# POWER_SUPPLY_20-100V_Relay.net
KiCad netlist of a schematic drawn in Altium Designer
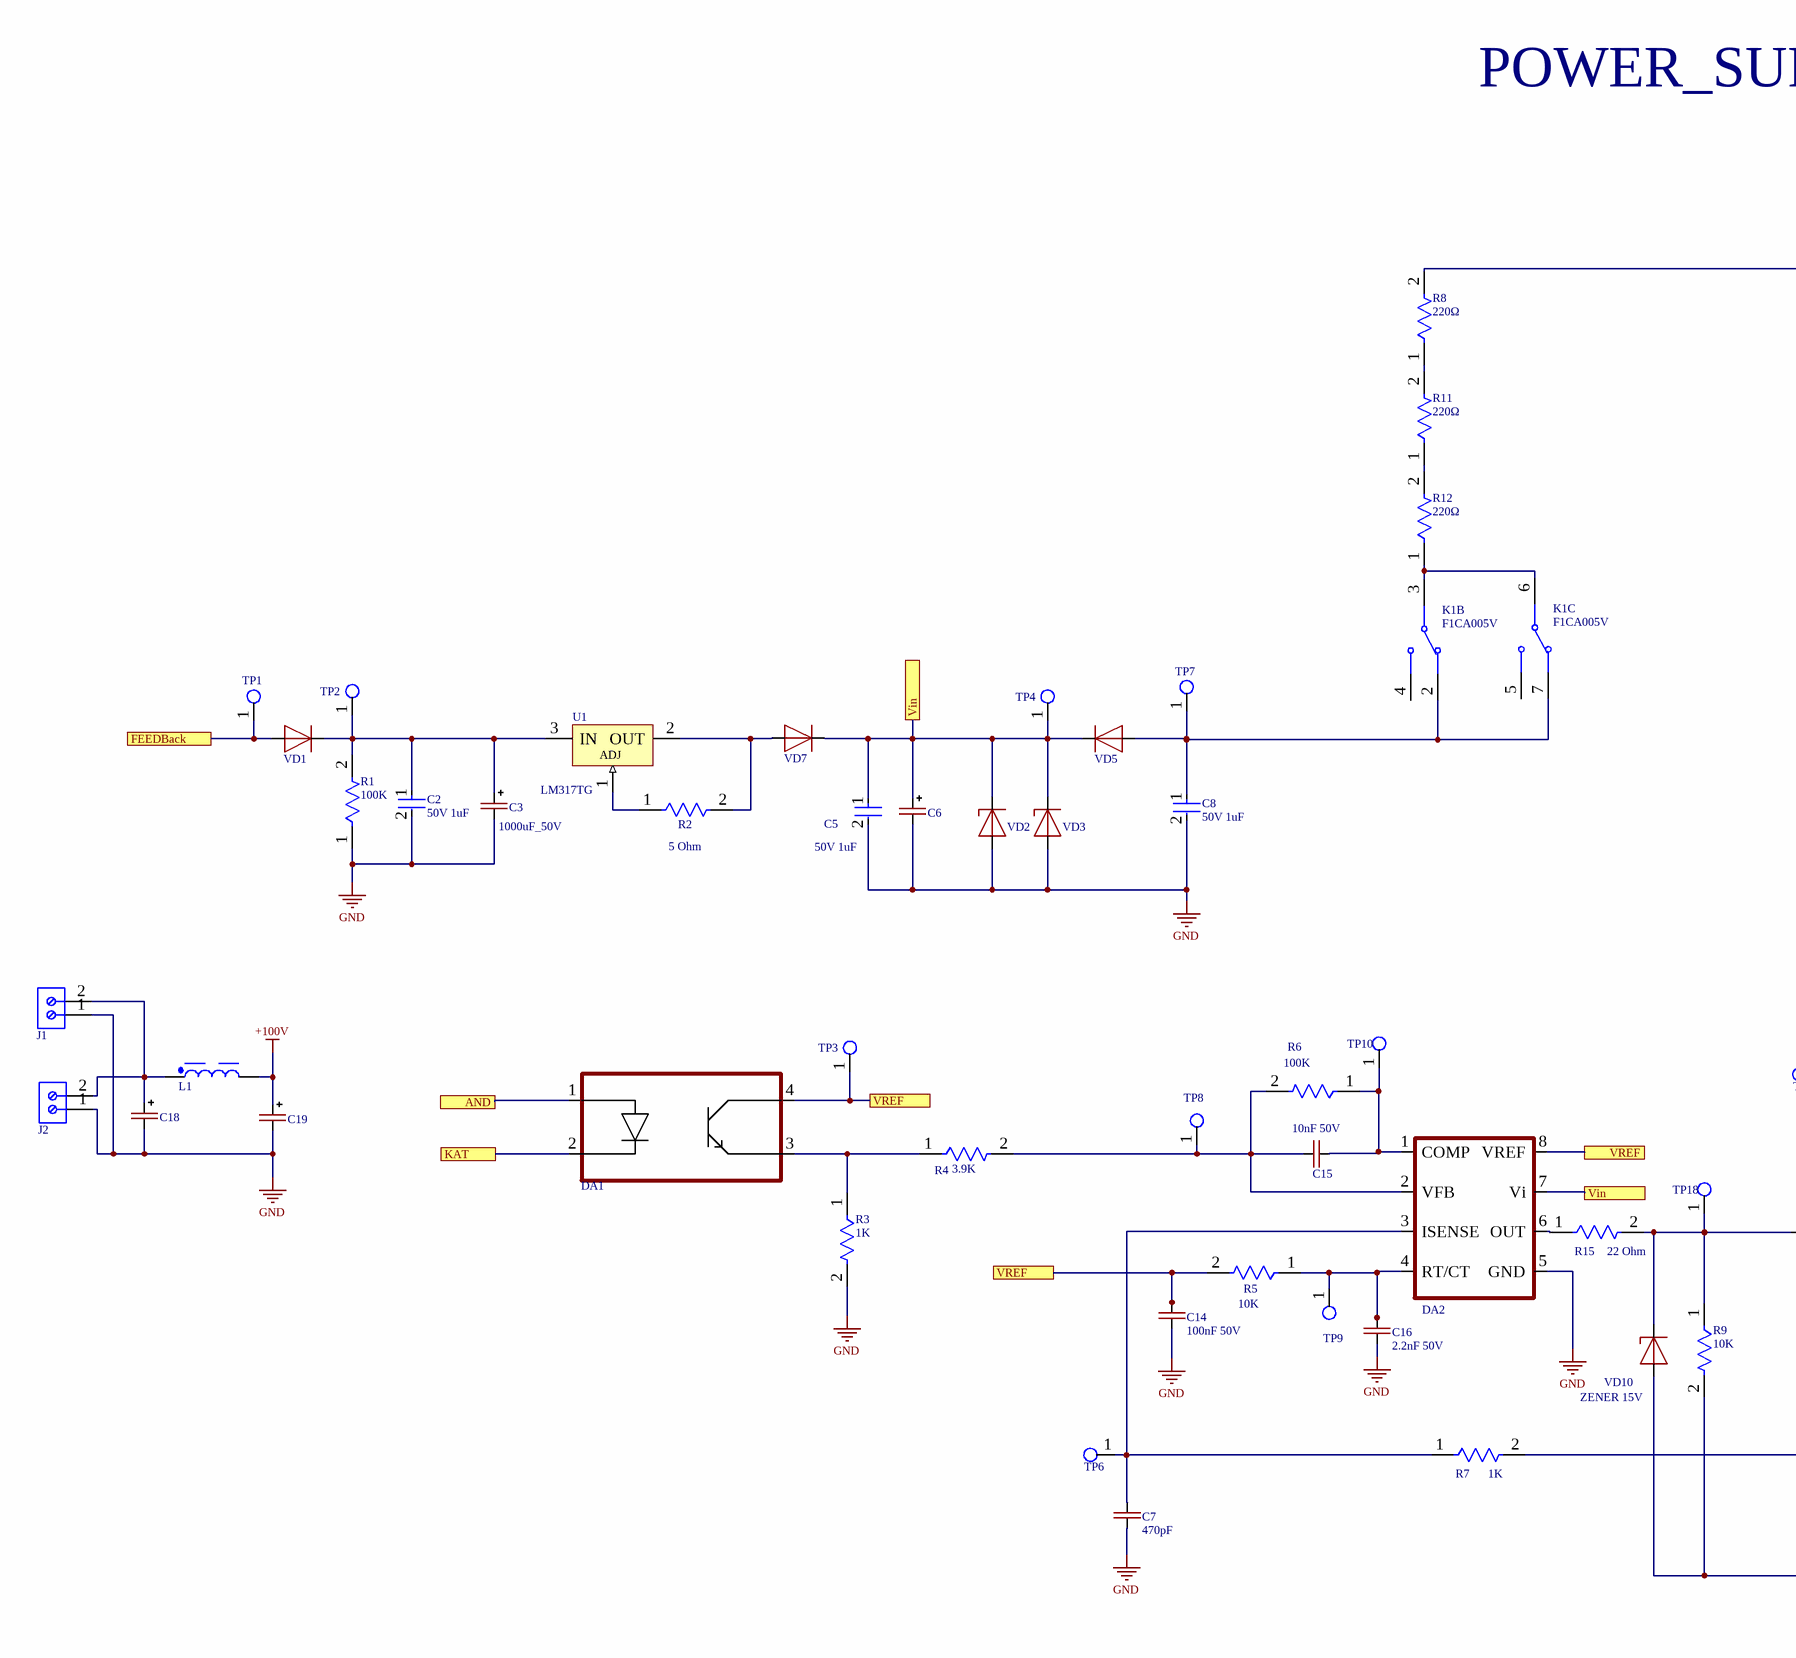
[diagram p0: POWER_SUPPLY_20-100V(Relay).SchDoc, left]
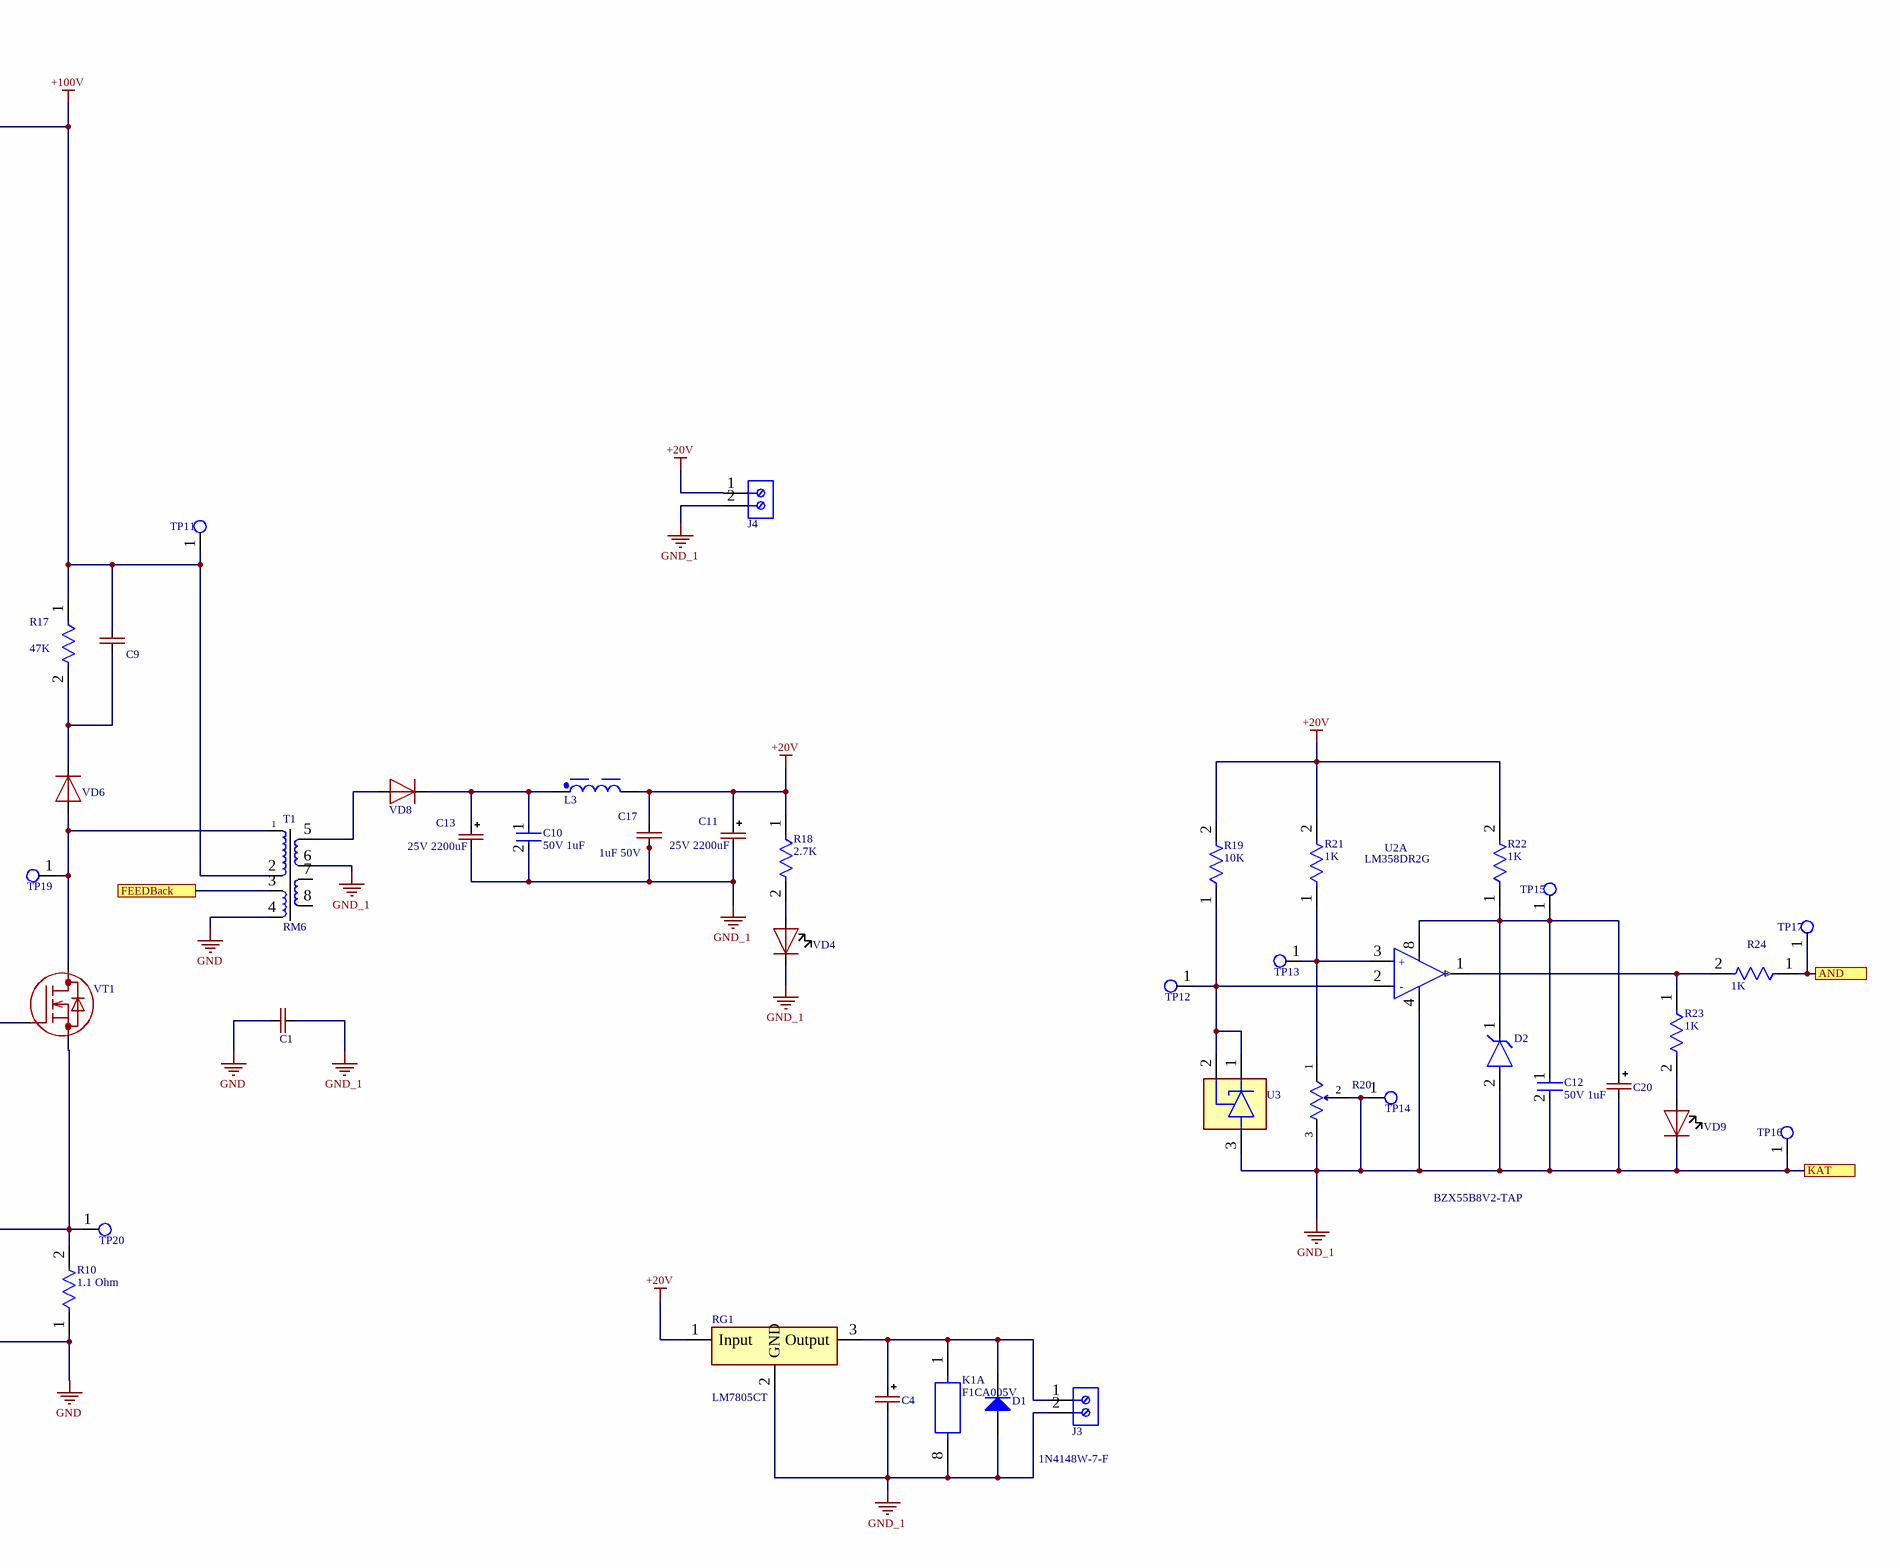
[diagram p1: POWER_SUPPLY_20-100V(Relay).SchDoc, right]

(export (version "E")
  (design (tool "Eeschema 10.0.6"))
  (components
    (comp (ref "C1")
      (value "CAP-NON-POLAR")
      (footprint "CAP-V5")
      (libsource (lib "2200pF") (part "CAP-NON-POLAR"))
    )
    (comp (ref "C2")
      (value "50V 1uF")
      (footprint "FP-C0805C-DN-IPC_A")
      (description "CAP CER 0.22UF 50V X7R 0805")
      (fields
        (field (name "MANUFACTURER") "KEMET")
        (field (name "OCTOPART") "https://octopart.com/c0805c224k5ractu-kemet-144670")
      )
      (libsource (lib "Pasive_components") (part "CMP-1036-04552-2"))
    )
    (comp (ref "C3")
      (value "1000uF_50V")
      (footprint "CAPPOL-12x25")
      (description "1000uF_50V  12x25(13x26mm)")
      (libsource (lib "PASSIVE_COMPONENTS") (part "CAP-POLAR"))
    )
    (comp (ref "C4")
      (value "CAP-POLAR")
      (footprint "CAP-TAN-D")
      (libsource (lib "PASSIVE_COMPONENTS") (part "CAP-POLAR"))
    )
    (comp (ref "C5")
      (value "50V 1uF")
      (footprint "FP-C0805C-DN-IPC_A")
      (description "CAP CER 0.22UF 50V X7R 0805")
      (fields
        (field (name "MANUFACTURER") "KEMET")
        (field (name "OCTOPART") "https://octopart.com/c0805c224k5ractu-kemet-144670")
      )
      (libsource (lib "Pasive_components") (part "CMP-1036-04552-2"))
    )
    (comp (ref "C6")
      (value "CAP-POLAR")
      (footprint "CAPPOL-12x25")
      (libsource (lib "PASSIVE_COMPONENTS") (part "CAP-POLAR"))
    )
    (comp (ref "C7")
      (value "470pF")
      (footprint "CAP-0805")
      (libsource (lib "PASSIVE_COMPONENTS") (part "CAP-NON-POLAR"))
    )
    (comp (ref "C8")
      (value "50V 1uF")
      (footprint "FP-C0805C-DN-IPC_A")
      (description "CAP CER 0.22UF 50V X7R 0805")
      (fields
        (field (name "MANUFACTURER") "KEMET")
        (field (name "OCTOPART") "https://octopart.com/c0805c224k5ractu-kemet-144670")
      )
      (libsource (lib "Pasive_components") (part "CMP-1036-04552-2"))
    )
    (comp (ref "C9")
      (value "CAP-NON-POLAR")
      (footprint "CAP-V5")
      (libsource (lib "2200pF") (part "CAP-NON-POLAR"))
    )
    (comp (ref "C10")
      (value "50V 1uF")
      (footprint "FP-C0805C-DN-IPC_A")
      (description "CAP CER 0.22UF 50V X7R 0805")
      (fields
        (field (name "MANUFACTURER") "KEMET")
        (field (name "OCTOPART") "https://octopart.com/c0805c224k5ractu-kemet-144670")
      )
      (libsource (lib "Pasive_components") (part "CMP-1036-04552-2"))
    )
    (comp (ref "C11")
      (value "25V 2200uF")
      (footprint "CAPPOL-12x25")
      (libsource (lib "12.5X25") (part "CAP-POLAR"))
    )
    (comp (ref "C12")
      (value "50V 1uF")
      (footprint "FP-C0805C-DN-IPC_A")
      (description "CAP CER 0.22UF 50V X7R 0805")
      (fields
        (field (name "MANUFACTURER") "KEMET")
        (field (name "OCTOPART") "https://octopart.com/c0805c224k5ractu-kemet-144670")
      )
      (libsource (lib "Pasive_components") (part "CMP-1036-04552-2"))
    )
    (comp (ref "C13")
      (value "25V 2200uF")
      (footprint "CAPPOL-12x25")
      (libsource (lib "12.5X25") (part "CAP-POLAR"))
    )
    (comp (ref "C14")
      (value "100nF 50V")
      (footprint "CAP-0805")
      (libsource (lib "PASSIVE_COMPONENTS") (part "CAP-NON-POLAR"))
    )
    (comp (ref "C15")
      (value "10nF 50V")
      (footprint "CAP-0805")
      (libsource (lib "PASSIVE_COMPONENTS") (part "CAP-NON-POLAR"))
    )
    (comp (ref "C16")
      (value "2.2nF 50V")
      (footprint "CAP-0805")
      (libsource (lib "PASSIVE_COMPONENTS") (part "CAP-NON-POLAR"))
    )
    (comp (ref "C17")
      (value "1uF 50V")
      (footprint "CAP-0805")
      (libsource (lib "PASSIVE_COMPONENTS") (part "CAP-NON-POLAR"))
    )
    (comp (ref "C18")
      (value "CAP-POLAR")
      (footprint "CAPPOL-10x20")
      (libsource (lib "PASSIVE_COMPONENTS") (part "CAP-POLAR"))
    )
    (comp (ref "C19")
      (value "CAP-POLAR")
      (footprint "CAPPOL-10x20")
      (libsource (lib "PASSIVE_COMPONENTS") (part "CAP-POLAR"))
    )
    (comp (ref "C20")
      (value "CAP-POLAR")
      (footprint "CAP-TAN-D")
      (libsource (lib "PASSIVE_COMPONENTS") (part "CAP-POLAR"))
    )
    (comp (ref "D1")
      (value "1N4148W-7-F")
      (footprint "DIOD-SOD123-2_V")
      (description "Fast Switching Diode, 100 V, 0.15 A, -65 to 150 degC, 2-Pin?SOD123, RoHS, Tape and Reel")
      (fields (field (name "MANUFACTURER") "DiodesIncorporated"))
      (libsource (lib "Diodes") (part "1N4148"))
    )
    (comp (ref "D2")
      (value "BZX55B8V2-TAP")
      (footprint "FP-SB-V-3906_04-031_4-MFG")
      (description "DIODE ZENER 8.2V 500MW DO35")
      (fields (field (name "TOLERANCE") "2%"))
      (libsource (lib "Altium Content Vault") (part "f813f71cba58e380607f5dd3caf9714"))
    )
    (comp (ref "DA1") (value "PC817") (footprint "4-SMD") (libsource (lib "PC817") (part "PC817")))
    (comp (ref "DA2") (value "UC3842B") (footprint "SOIC8-150") (libsource (lib "UC3842B") (part "UC3842B")))
    (comp (ref "J1")
      (value "691101710002")
      (footprint "691101710002")
      (description "WR-TBL Series 101 Horizontal Entry Modular, THT, pitch 5mm, 2p")
      (fields (field (name "MANUFACTURER") "Wurth Elektronik"))
      (libsource (lib "Altium_WR-TBL (rev23d)") (part "691101710002"))
    )
    (comp (ref "J2")
      (value "691101710002")
      (footprint "691101710002")
      (description "WR-TBL Series 101 Horizontal Entry Modular, THT, pitch 5mm, 2p")
      (fields (field (name "MANUFACTURER") "Wurth Elektronik"))
      (libsource (lib "Altium_WR-TBL (rev23d)") (part "691101710002"))
    )
    (comp (ref "J3")
      (value "691101710002")
      (footprint "691101710002")
      (description "WR-TBL Series 101 Horizontal Entry Modular, THT, pitch 5mm, 2p")
      (fields (field (name "MANUFACTURER") "Wurth Elektronik"))
      (libsource (lib "Altium_WR-TBL (rev23d)") (part "691101710002"))
    )
    (comp (ref "J4")
      (value "691101710002")
      (footprint "691101710002")
      (description "WR-TBL Series 101 Horizontal Entry Modular, THT, pitch 5mm, 2p")
      (fields (field (name "MANUFACTURER") "Wurth Elektronik"))
      (libsource (lib "Altium_WR-TBL (rev23d)") (part "691101710002"))
    )
    (comp (ref "K1")
      (value "F1CA005V")
      (footprint "V23079-A1001-B301")
      (libsource (lib "Relays") (part "F1CA005V"))
    )
    (comp (ref "L1")
      (value "470µH, 0.36A")
      (footprint "WE-PD2_7850")
      (description "WE-PD2 SMT Power Inductor, size 7850, 470µH, 0.36A, 1.96Ω")
      (fields
        (field (name "MANUFACTURER PART NUMBER") "744775247")
        (field (name "MANUFACTURER") "Wurth Elektronik")
      )
      (libsource (lib "WE-PD2 (rev22d)") (part "744775247"))
    )
    (comp (ref "L3")
      (value "470µH, 0.36A")
      (footprint "WE-PD2_7850")
      (description "WE-PD2 SMT Power Inductor, size 7850, 470µH, 0.36A, 1.96Ω")
      (fields
        (field (name "MANUFACTURER PART NUMBER") "744775247")
        (field (name "MANUFACTURER") "Wurth Elektronik")
      )
      (libsource (lib "WE-PD2 (rev22d)") (part "744775247"))
    )
    (comp (ref "R1")
      (value "100K")
      (footprint "RES-0805")
      (libsource (lib "PASSIVE_COMPONENTS") (part "RES-CONST"))
    )
    (comp (ref "R2")
      (value "5 Ohm")
      (footprint "RES-1206")
      (libsource (lib "PASSIVE_COMPONENTS") (part "RES-CONST"))
    )
    (comp (ref "R3")
      (value "1K")
      (footprint "RES-0805")
      (libsource (lib "PASSIVE_COMPONENTS") (part "RES-CONST"))
    )
    (comp (ref "R4")
      (value "3.9K")
      (footprint "RES-0805")
      (libsource (lib "PASSIVE_COMPONENTS") (part "RES-CONST"))
    )
    (comp (ref "R5")
      (value "10K")
      (footprint "RES-0805")
      (libsource (lib "PASSIVE_COMPONENTS") (part "RES-CONST"))
    )
    (comp (ref "R6")
      (value "100K")
      (footprint "RES-0805")
      (libsource (lib "PASSIVE_COMPONENTS") (part "RES-CONST"))
    )
    (comp (ref "R7")
      (value "1K")
      (footprint "RES-0805")
      (libsource (lib "PASSIVE_COMPONENTS") (part "RES-CONST"))
    )
    (comp (ref "R8")
      (value "220Ω")
      (footprint "RES-2512")
      (libsource (lib "PASSIVE_COMPONENTS") (part "RES-CONST"))
    )
    (comp (ref "R9")
      (value "10K")
      (footprint "RES-0805")
      (libsource (lib "PASSIVE_COMPONENTS") (part "RES-CONST"))
    )
    (comp (ref "R10")
      (value "1.1 Ohm")
      (footprint "RES-2W")
      (libsource (lib "PASSIVE_COMPONENTS") (part "RES-CONST"))
    )
    (comp (ref "R11")
      (value "220Ω")
      (footprint "RES-2512")
      (libsource (lib "PASSIVE_COMPONENTS") (part "RES-CONST"))
    )
    (comp (ref "R12")
      (value "220Ω")
      (footprint "RES-2512")
      (libsource (lib "PASSIVE_COMPONENTS") (part "RES-CONST"))
    )
    (comp (ref "R15")
      (value "22 Ohm")
      (footprint "RES-0805")
      (libsource (lib "PASSIVE_COMPONENTS") (part "RES-CONST"))
    )
    (comp (ref "R17")
      (value "47K")
      (footprint "RES-2512")
      (libsource (lib "PASSIVE_COMPONENTS") (part "RES-CONST"))
    )
    (comp (ref "R18")
      (value "2.7K")
      (footprint "RES-0805")
      (libsource (lib "PASSIVE_COMPONENTS") (part "RES-CONST"))
    )
    (comp (ref "R19")
      (value "10K")
      (footprint "RES-0805")
      (libsource (lib "PASSIVE_COMPONENTS") (part "RES-CONST"))
    )
    (comp (ref "R20")
      (value "3296W-1-202LF")
      (footprint "Bourns_3296W_MFG")
      (libsource (lib "Pasive_components") (part "3296W-1-202LF"))
    )
    (comp (ref "R21")
      (value "1K")
      (footprint "RES-0805")
      (libsource (lib "PASSIVE_COMPONENTS") (part "RES-CONST"))
    )
    (comp (ref "R22")
      (value "1K")
      (footprint "RES-0805")
      (libsource (lib "PASSIVE_COMPONENTS") (part "RES-CONST"))
    )
    (comp (ref "R23")
      (value "1K")
      (footprint "RES-0805")
      (libsource (lib "PASSIVE_COMPONENTS") (part "RES-CONST"))
    )
    (comp (ref "R24")
      (value "1K")
      (footprint "RES-0805")
      (libsource (lib "PASSIVE_COMPONENTS") (part "RES-CONST"))
    )
    (comp (ref "RG1")
      (value "LM7805CT")
      (footprint "SOT-223-3")
      (description "REG IC REG LINEAR 5V 1A TO220AB")
      (fields
        (field (name "MANUFACTURER") "Fairchild")
        (field (name "MOUSER PART NUMBER") "512-LM7805CT")
        (field (name "PART NUMBER") "LM7805CT")
      )
      (libsource (lib "Integrated_Circuts") (part "LM7805CT"))
    )
    (comp (ref "T1")
      (value "RM6")
      (footprint "TRANS_RM6")
      (libsource (lib "Transformers") (part "Trans_RM6"))
    )
    (comp (ref "TP1")
      (value "Test_Point_PCB")
      (footprint "Test_Point")
      (description "Test_Point")
      (libsource (lib "Test_Point") (part "TP_PCB?"))
    )
    (comp (ref "TP2")
      (value "Test_Point_PCB")
      (footprint "Test_Point")
      (description "Test_Point")
      (libsource (lib "Test_Point") (part "TP_PCB?"))
    )
    (comp (ref "TP3")
      (value "Test_Point_PCB")
      (footprint "Test_Point")
      (description "Test_Point")
      (libsource (lib "Test_Point") (part "TP_PCB?"))
    )
    (comp (ref "TP4")
      (value "Test_Point_PCB")
      (footprint "Test_Point")
      (description "Test_Point")
      (libsource (lib "Test_Point") (part "TP_PCB?"))
    )
    (comp (ref "TP6")
      (value "Test_Point_PCB")
      (footprint "Test_Point")
      (description "Test_Point")
      (libsource (lib "Test_Point") (part "TP_PCB?"))
    )
    (comp (ref "TP7")
      (value "Test_Point_PCB")
      (footprint "Test_Point")
      (description "Test_Point")
      (libsource (lib "Test_Point") (part "TP_PCB?"))
    )
    (comp (ref "TP8")
      (value "Test_Point_PCB")
      (footprint "Test_Point")
      (description "Test_Point")
      (libsource (lib "Test_Point") (part "TP_PCB?"))
    )
    (comp (ref "TP9")
      (value "Test_Point_PCB")
      (footprint "Test_Point")
      (description "Test_Point")
      (libsource (lib "Test_Point") (part "TP_PCB?"))
    )
    (comp (ref "TP10")
      (value "Test_Point_PCB")
      (footprint "Test_Point")
      (description "Test_Point")
      (libsource (lib "Test_Point") (part "TP_PCB?"))
    )
    (comp (ref "TP11")
      (value "Test_Point_PCB")
      (footprint "Test_Point")
      (description "Test_Point")
      (libsource (lib "Test_Point") (part "TP_PCB?"))
    )
    (comp (ref "TP12")
      (value "Test_Point_PCB")
      (footprint "Test_Point")
      (description "Test_Point")
      (libsource (lib "Test_Point") (part "TP_PCB?"))
    )
    (comp (ref "TP13")
      (value "Test_Point_PCB")
      (footprint "Test_Point")
      (description "Test_Point")
      (libsource (lib "Test_Point") (part "TP_PCB?"))
    )
    (comp (ref "TP14")
      (value "Test_Point_PCB")
      (footprint "Test_Point")
      (description "Test_Point")
      (libsource (lib "Test_Point") (part "TP_PCB?"))
    )
    (comp (ref "TP15")
      (value "Test_Point_PCB")
      (footprint "Test_Point")
      (description "Test_Point")
      (libsource (lib "Test_Point") (part "TP_PCB?"))
    )
    (comp (ref "TP16")
      (value "Test_Point_PCB")
      (footprint "Test_Point")
      (description "Test_Point")
      (libsource (lib "Test_Point") (part "TP_PCB?"))
    )
    (comp (ref "TP17")
      (value "Test_Point_PCB")
      (footprint "Test_Point")
      (description "Test_Point")
      (libsource (lib "Test_Point") (part "TP_PCB?"))
    )
    (comp (ref "TP18")
      (value "Test_Point_PCB")
      (footprint "Test_Point")
      (description "Test_Point")
      (libsource (lib "Test_Point") (part "TP_PCB?"))
    )
    (comp (ref "TP19")
      (value "Test_Point_PCB")
      (footprint "Test_Point")
      (description "Test_Point")
      (libsource (lib "Test_Point") (part "TP_PCB?"))
    )
    (comp (ref "TP20")
      (value "Test_Point_PCB")
      (footprint "Test_Point")
      (description "Test_Point")
      (libsource (lib "Test_Point") (part "TP_PCB?"))
    )
    (comp (ref "U1")
      (value "LM317TG")
      (footprint "TO-220_Bended_Rad")
      (libsource (lib "LM317TG") (part "LM317TG"))
    )
    (comp (ref "U2")
      (value "LM358DR2G")
      (footprint "FP-751-07-IPC_C")
      (description "IC OPAMP GP 2 CIRCUIT 8SOIC")
      (libsource (lib "Altium Content Vault") (part "992a6607d1d88c80ee6b45e5ba6cb1b"))
    )
    (comp (ref "U3")
      (value "TL431")
      (footprint "TL431_SOT-23-3(MGF)")
      (description "TL431_SOT-23-3")
      (libsource (lib "TL431") (part "TL431_SOT-23-3"))
    )
    (comp (ref "VD1") (value "DIODE") (footprint "DO-214AC, SMA") (libsource (lib "DO214") (part "DIODE")))
    (comp (ref "VD2") (value "ZENER") (footprint "DO-017AA") (libsource (lib "ZENER") (part "ZENER")))
    (comp (ref "VD3") (value "ZENER") (footprint "DO-017AA") (libsource (lib "ZENER") (part "ZENER")))
    (comp (ref "VD4") (value "LED") (footprint "LED-0603") (libsource (lib "LED") (part "LED")))
    (comp (ref "VD5") (value "DIODE") (footprint "DO-214AC, SMA") (libsource (lib "DO214") (part "DIODE")))
    (comp (ref "VD6") (value "DIODE") (footprint "DO-214AC, SMA") (libsource (lib "DO214") (part "DIODE")))
    (comp (ref "VD7") (value "DIODE") (footprint "DO-214AC, SMA") (libsource (lib "DO214") (part "DIODE")))
    (comp (ref "VD8") (value "DIODE") (footprint "DO-214AC, SMA") (libsource (lib "DO214") (part "DIODE")))
    (comp (ref "VD9") (value "LED") (footprint "LED-0603") (libsource (lib "LED") (part "LED")))
    (comp (ref "VD10") (value "ZENER 15V") (footprint "DO-017AA") (libsource (lib "ZENER") (part "ZENER")))
    (comp (ref "VT1")
      (value "MOSFET-N-GDS")
      (footprint "TO-220_Bended_Rad")
      (libsource (lib "IRF640") (part "MOSFET-N-GDS"))
    )
  )
  (nets
    (net (code "1") (name "+20V") (class "Default")
      (node (ref "C11") (pin "1") (pinfunction "+_1") (pintype "passive"))
      (node (ref "C17") (pin "2") (pinfunction "2_2") (pintype "passive"))
      (node (ref "J4") (pin "1") (pinfunction "1_1") (pintype "passive"))
      (node (ref "L3") (pin "2") (pinfunction "2_2") (pintype "passive"))
      (node (ref "R18") (pin "1") (pinfunction "1_1") (pintype "passive"))
      (node (ref "R19") (pin "2") (pinfunction "2_2") (pintype "passive"))
      (node (ref "R21") (pin "2") (pinfunction "2_2") (pintype "passive"))
      (node (ref "R22") (pin "2") (pinfunction "2_2") (pintype "passive"))
      (node (ref "RG1") (pin "1") (pinfunction "Input_1") (pintype "power_in"))
    )
    (net (code "2") (name "+100V") (class "Default")
      (node (ref "C19") (pin "1") (pinfunction "+_1") (pintype "passive"))
      (node (ref "C9") (pin "2") (pinfunction "2_2") (pintype "passive"))
      (node (ref "L1") (pin "2") (pinfunction "2_2") (pintype "passive"))
      (node (ref "R17") (pin "1") (pinfunction "1_1") (pintype "passive"))
      (node (ref "R8") (pin "2") (pinfunction "2_2") (pintype "passive"))
      (node (ref "T1") (pin "2") (pinfunction "2_2") (pintype "passive"))
      (node (ref "TP11") (pin "1") (pinfunction "G9_1") (pintype "passive"))
    )
    (net (code "3") (name "/AND") (class "Default")
      (node (ref "DA1") (pin "1") (pinfunction "ANODE_1") (pintype "passive"))
      (node (ref "R24") (pin "1") (pinfunction "1_1") (pintype "passive"))
      (node (ref "TP17") (pin "1") (pinfunction "G9_1") (pintype "passive"))
    )
    (net (code "4") (name "/FEEDBack") (class "Default")
      (node (ref "T1") (pin "3") (pinfunction "3_3") (pintype "passive"))
      (node (ref "TP1") (pin "1") (pinfunction "G9_1") (pintype "passive"))
      (node (ref "VD1") (pin "2") (pinfunction "A_2") (pintype "passive"))
    )
    (net (code "5") (name "/VREF") (class "Default")
      (node (ref "C14") (pin "2") (pinfunction "2_2") (pintype "passive"))
      (node (ref "DA1") (pin "4") (pinfunction "COLLECTOR_4") (pintype "passive"))
      (node (ref "DA2") (pin "8") (pinfunction "VREF_8") (pintype "passive"))
      (node (ref "R5") (pin "2") (pinfunction "2_2") (pintype "passive"))
      (node (ref "TP3") (pin "1") (pinfunction "G9_1") (pintype "passive"))
    )
    (net (code "6") (name "/Vin") (class "Default")
      (node (ref "C5") (pin "1") (pinfunction "1_1") (pintype "passive"))
      (node (ref "C6") (pin "1") (pinfunction "+_1") (pintype "passive"))
      (node (ref "DA2") (pin "7") (pinfunction "Vi_7") (pintype "passive"))
      (node (ref "TP4") (pin "1") (pinfunction "G9_1") (pintype "passive"))
      (node (ref "VD2") (pin "1") (pinfunction "C_1") (pintype "passive"))
      (node (ref "VD3") (pin "1") (pinfunction "C_1") (pintype "passive"))
      (node (ref "VD5") (pin "1") (pinfunction "C_1") (pintype "passive"))
      (node (ref "VD7") (pin "1") (pinfunction "C_1") (pintype "passive"))
    )
    (net (code "7") (name "GND") (class "Default")
      (node (ref "C1") (pin "1") (pinfunction "1_1") (pintype "passive"))
      (node (ref "C14") (pin "1") (pinfunction "1_1") (pintype "passive"))
      (node (ref "C16") (pin "1") (pinfunction "1_1") (pintype "passive"))
      (node (ref "C18") (pin "2") (pinfunction "-_2") (pintype "passive"))
      (node (ref "C19") (pin "2") (pinfunction "-_2") (pintype "passive"))
      (node (ref "C2") (pin "2") (pinfunction "2_2") (pintype "passive"))
      (node (ref "C3") (pin "2") (pinfunction "-_2") (pintype "passive"))
      (node (ref "C5") (pin "2") (pinfunction "2_2") (pintype "passive"))
      (node (ref "C6") (pin "2") (pinfunction "-_2") (pintype "passive"))
      (node (ref "C7") (pin "1") (pinfunction "1_1") (pintype "passive"))
      (node (ref "C8") (pin "2") (pinfunction "2_2") (pintype "passive"))
      (node (ref "DA2") (pin "5") (pinfunction "GND_5") (pintype "passive"))
      (node (ref "J1") (pin "1") (pinfunction "1_1") (pintype "passive"))
      (node (ref "J2") (pin "1") (pinfunction "1_1") (pintype "passive"))
      (node (ref "R1") (pin "1") (pinfunction "1_1") (pintype "passive"))
      (node (ref "R10") (pin "1") (pinfunction "1_1") (pintype "passive"))
      (node (ref "R3") (pin "2") (pinfunction "2_2") (pintype "passive"))
      (node (ref "R9") (pin "2") (pinfunction "2_2") (pintype "passive"))
      (node (ref "T1") (pin "4") (pinfunction "4_4") (pintype "passive"))
      (node (ref "VD10") (pin "2") (pinfunction "A_2") (pintype "passive"))
      (node (ref "VD2") (pin "2") (pinfunction "A_2") (pintype "passive"))
      (node (ref "VD3") (pin "2") (pinfunction "A_2") (pintype "passive"))
    )
    (net (code "8") (name "GND_1") (class "Default")
      (node (ref "C1") (pin "2") (pinfunction "2_2") (pintype "passive"))
      (node (ref "C10") (pin "2") (pinfunction "2_2") (pintype "passive"))
      (node (ref "C11") (pin "2") (pinfunction "-_2") (pintype "passive"))
      (node (ref "C12") (pin "2") (pinfunction "2_2") (pintype "passive"))
      (node (ref "C13") (pin "2") (pinfunction "-_2") (pintype "passive"))
      (node (ref "C17") (pin "1") (pinfunction "1_1") (pintype "passive"))
      (node (ref "C20") (pin "2") (pinfunction "-_2") (pintype "passive"))
      (node (ref "C4") (pin "2") (pinfunction "-_2") (pintype "passive"))
      (node (ref "D1") (pin "2") (pinfunction "A_2") (pintype "passive"))
      (node (ref "D2") (pin "2") (pinfunction "A_2") (pintype "passive"))
      (node (ref "DA1") (pin "2") (pinfunction "CATHODE_2") (pintype "passive"))
      (node (ref "J3") (pin "2") (pinfunction "2_2") (pintype "passive"))
      (node (ref "J4") (pin "2") (pinfunction "2_2") (pintype "passive"))
      (node (ref "K1") (pin "8") (pinfunction "8_8") (pintype "passive"))
      (node (ref "R20") (pin "2") (pinfunction "WIPER_2") (pintype "passive"))
      (node (ref "R20") (pin "3") (pinfunction "CW_3") (pintype "passive"))
      (node (ref "RG1") (pin "2") (pinfunction "GND_2") (pintype "power_in"))
      (node (ref "T1") (pin "6") (pinfunction "6_6") (pintype "passive"))
      (node (ref "TP14") (pin "1") (pinfunction "G9_1") (pintype "passive"))
      (node (ref "TP16") (pin "1") (pinfunction "G9_1") (pintype "passive"))
      (node (ref "U2") (pin "4") (pinfunction "VEE/GND_4") (pintype "power_in"))
      (node (ref "U3") (pin "3") (pinfunction "A_3") (pintype "passive"))
      (node (ref "VD4") (pin "1") (pinfunction "C_1") (pintype "passive"))
      (node (ref "VD9") (pin "1") (pinfunction "C_1") (pintype "passive"))
    )
    (net (code "9") (name "Net-(C3-+)") (class "Default")
      (node (ref "C2") (pin "1") (pinfunction "1_1") (pintype "passive"))
      (node (ref "C3") (pin "1") (pinfunction "+_1") (pintype "passive"))
      (node (ref "R1") (pin "2") (pinfunction "2_2") (pintype "passive"))
      (node (ref "TP2") (pin "1") (pinfunction "G9_1") (pintype "passive"))
      (node (ref "U1") (pin "3") (pinfunction "IN_3") (pintype "power_in"))
      (node (ref "VD1") (pin "1") (pinfunction "C_1") (pintype "passive"))
    )
    (net (code "10") (name "Net-(C4-+)") (class "Default")
      (node (ref "C4") (pin "1") (pinfunction "+_1") (pintype "passive"))
      (node (ref "D1") (pin "1") (pinfunction "K_1") (pintype "passive"))
      (node (ref "J3") (pin "1") (pinfunction "1_1") (pintype "passive"))
      (node (ref "K1") (pin "1") (pinfunction "1_1") (pintype "passive"))
      (node (ref "RG1") (pin "3") (pinfunction "Output_3") (pintype "passive"))
    )
    (net (code "11") (name "Net-(C13-+)") (class "Default")
      (node (ref "C10") (pin "1") (pinfunction "1_1") (pintype "passive"))
      (node (ref "C13") (pin "1") (pinfunction "+_1") (pintype "passive"))
      (node (ref "L3") (pin "1") (pinfunction "1_1") (pintype "passive"))
      (node (ref "VD8") (pin "1") (pinfunction "C_1") (pintype "passive"))
    )
    (net (code "12") (name "Net-(C18-+)") (class "Default")
      (node (ref "C18") (pin "1") (pinfunction "+_1") (pintype "passive"))
      (node (ref "J1") (pin "2") (pinfunction "2_2") (pintype "passive"))
      (node (ref "J2") (pin "2") (pinfunction "2_2") (pintype "passive"))
      (node (ref "L1") (pin "1") (pinfunction "1_1") (pintype "passive"))
    )
    (net (code "13") (name "Net-(C20-+)") (class "Default")
      (node (ref "C12") (pin "1") (pinfunction "1_1") (pintype "passive"))
      (node (ref "C20") (pin "1") (pinfunction "+_1") (pintype "passive"))
      (node (ref "D2") (pin "1") (pinfunction "C_1") (pintype "passive"))
      (node (ref "R22") (pin "1") (pinfunction "1_1") (pintype "passive"))
      (node (ref "TP15") (pin "1") (pinfunction "G9_1") (pintype "passive"))
      (node (ref "U2") (pin "8") (pinfunction "VCC_8") (pintype "power_in"))
    )
    (net (code "14") (name "Net-(DA1-EMITTER)") (class "Default")
      (node (ref "DA1") (pin "3") (pinfunction "EMITTER_3") (pintype "passive"))
      (node (ref "R3") (pin "1") (pinfunction "1_1") (pintype "passive"))
      (node (ref "R4") (pin "1") (pinfunction "1_1") (pintype "passive"))
    )
    (net (code "15") (name "Net-(DA2-COMP)") (class "Default")
      (node (ref "C15") (pin "2") (pinfunction "2_2") (pintype "passive"))
      (node (ref "DA2") (pin "1") (pinfunction "COMP_1") (pintype "passive"))
      (node (ref "R6") (pin "1") (pinfunction "1_1") (pintype "passive"))
      (node (ref "TP10") (pin "1") (pinfunction "G9_1") (pintype "passive"))
    )
    (net (code "16") (name "Net-(DA2-ISENSE)") (class "Default")
      (node (ref "C7") (pin "2") (pinfunction "2_2") (pintype "passive"))
      (node (ref "DA2") (pin "3") (pinfunction "ISENSE_3") (pintype "passive"))
      (node (ref "R7") (pin "1") (pinfunction "1_1") (pintype "passive"))
      (node (ref "TP6") (pin "1") (pinfunction "G9_1") (pintype "passive"))
    )
    (net (code "17") (name "Net-(DA2-OUT)") (class "Default")
      (node (ref "DA2") (pin "6") (pinfunction "OUT_6") (pintype "passive"))
      (node (ref "R15") (pin "1") (pinfunction "1_1") (pintype "passive"))
    )
    (net (code "18") (name "Net-(DA2-RT{slash}CT)") (class "Default")
      (node (ref "C16") (pin "2") (pinfunction "2_2") (pintype "passive"))
      (node (ref "DA2") (pin "4") (pinfunction "RT/CT_4") (pintype "passive"))
      (node (ref "R5") (pin "1") (pinfunction "1_1") (pintype "passive"))
      (node (ref "TP9") (pin "1") (pinfunction "G9_1") (pintype "passive"))
    )
    (net (code "19") (name "Net-(DA2-VFB)") (class "Default")
      (node (ref "C15") (pin "1") (pinfunction "1_1") (pintype "passive"))
      (node (ref "DA2") (pin "2") (pinfunction "VFB_2") (pintype "passive"))
      (node (ref "R4") (pin "2") (pinfunction "2_2") (pintype "passive"))
      (node (ref "R6") (pin "2") (pinfunction "2_2") (pintype "passive"))
      (node (ref "TP8") (pin "1") (pinfunction "G9_1") (pintype "passive"))
    )
    (net (code "20") (name "Net-(K1-Pad3)") (class "Default")
      (node (ref "K1") (pin "3") (pinfunction "3_3") (pintype "passive"))
      (node (ref "K1") (pin "6") (pinfunction "6_6") (pintype "passive"))
      (node (ref "R12") (pin "1") (pinfunction "1_1") (pintype "passive"))
    )
    (net (code "21") (name "Net-(R11-Pad1)") (class "Default")
      (node (ref "R11") (pin "1") (pinfunction "1_1") (pintype "passive"))
      (node (ref "R12") (pin "2") (pinfunction "2_2") (pintype "passive"))
    )
    (net (code "22") (name "Net-(R11-Pad2)") (class "Default")
      (node (ref "R11") (pin "2") (pinfunction "2_2") (pintype "passive"))
      (node (ref "R8") (pin "1") (pinfunction "1_1") (pintype "passive"))
    )
    (net (code "23") (name "Net-(R20-CCW)") (class "Default")
      (node (ref "R20") (pin "1") (pinfunction "CCW_1") (pintype "passive"))
      (node (ref "R21") (pin "1") (pinfunction "1_1") (pintype "passive"))
      (node (ref "TP13") (pin "1") (pinfunction "G9_1") (pintype "passive"))
      (node (ref "U2") (pin "3") (pinfunction "INPUT_A+_3") (pintype "tri_state"))
    )
    (net (code "24") (name "Net-(TP7-G9)") (class "Default")
      (node (ref "C8") (pin "1") (pinfunction "1_1") (pintype "passive"))
      (node (ref "K1") (pin "2") (pinfunction "2_2") (pintype "passive"))
      (node (ref "K1") (pin "7") (pinfunction "7_7") (pintype "passive"))
      (node (ref "TP7") (pin "1") (pinfunction "G9_1") (pintype "passive"))
      (node (ref "VD5") (pin "2") (pinfunction "A_2") (pintype "passive"))
    )
    (net (code "25") (name "Net-(TP12-G9)") (class "Default")
      (node (ref "R19") (pin "1") (pinfunction "1_1") (pintype "passive"))
      (node (ref "TP12") (pin "1") (pinfunction "G9_1") (pintype "passive"))
      (node (ref "U2") (pin "2") (pinfunction "INPUT_A-_2") (pintype "tri_state"))
      (node (ref "U3") (pin "1") (pinfunction "C_1") (pintype "passive"))
      (node (ref "U3") (pin "2") (pinfunction "REF_2") (pintype "passive"))
    )
    (net (code "26") (name "Net-(TP18-G9)") (class "Default")
      (node (ref "R15") (pin "2") (pinfunction "2_2") (pintype "passive"))
      (node (ref "R9") (pin "1") (pinfunction "1_1") (pintype "passive"))
      (node (ref "TP18") (pin "1") (pinfunction "G9_1") (pintype "passive"))
      (node (ref "VD10") (pin "1") (pinfunction "C_1") (pintype "passive"))
      (node (ref "VT1") (pin "1") (pinfunction "G_1") (pintype "passive"))
    )
    (net (code "27") (name "Net-(TP19-G9)") (class "Default")
      (node (ref "T1") (pin "1") (pinfunction "1_1") (pintype "passive"))
      (node (ref "TP19") (pin "1") (pinfunction "G9_1") (pintype "passive"))
      (node (ref "VD6") (pin "2") (pinfunction "A_2") (pintype "passive"))
      (node (ref "VT1") (pin "2") (pinfunction "D_2") (pintype "passive"))
    )
    (net (code "28") (name "Net-(TP20-G9)") (class "Default")
      (node (ref "R10") (pin "2") (pinfunction "2_2") (pintype "passive"))
      (node (ref "R7") (pin "2") (pinfunction "2_2") (pintype "passive"))
      (node (ref "TP20") (pin "1") (pinfunction "G9_1") (pintype "passive"))
      (node (ref "VT1") (pin "3") (pinfunction "S_3") (pintype "passive"))
    )
    (net (code "29") (name "Net-(U1-ADJ)") (class "Default")
      (node (ref "R2") (pin "1") (pinfunction "1_1") (pintype "passive"))
      (node (ref "U1") (pin "1") (pinfunction "ADJ_1") (pintype "input"))
    )
    (net (code "30") (name "Net-(U1-OUT)") (class "Default")
      (node (ref "R2") (pin "2") (pinfunction "2_2") (pintype "passive"))
      (node (ref "U1") (pin "2") (pinfunction "OUT_2") (pintype "power_in"))
      (node (ref "VD7") (pin "2") (pinfunction "A_2") (pintype "passive"))
    )
    (net (code "31") (name "Net-(U2A-OUTPUT_A)") (class "Default")
      (node (ref "R23") (pin "1") (pinfunction "1_1") (pintype "passive"))
      (node (ref "R24") (pin "2") (pinfunction "2_2") (pintype "passive"))
      (node (ref "U2") (pin "1") (pinfunction "OUTPUT_A_1") (pintype "output"))
    )
    (net (code "32") (name "Net-(VD4-A)") (class "Default")
      (node (ref "R18") (pin "2") (pinfunction "2_2") (pintype "passive"))
      (node (ref "VD4") (pin "2") (pinfunction "A_2") (pintype "passive"))
    )
    (net (code "33") (name "Net-(VD6-C)") (class "Default")
      (node (ref "C9") (pin "1") (pinfunction "1_1") (pintype "passive"))
      (node (ref "R17") (pin "2") (pinfunction "2_2") (pintype "passive"))
      (node (ref "VD6") (pin "1") (pinfunction "C_1") (pintype "passive"))
    )
    (net (code "34") (name "Net-(VD8-A)") (class "Default")
      (node (ref "T1") (pin "5") (pinfunction "5_5") (pintype "passive"))
      (node (ref "VD8") (pin "2") (pinfunction "A_2") (pintype "passive"))
    )
    (net (code "35") (name "Net-(VD9-A)") (class "Default")
      (node (ref "R23") (pin "2") (pinfunction "2_2") (pintype "passive"))
      (node (ref "VD9") (pin "2") (pinfunction "A_2") (pintype "passive"))
    )
    (net (code "36") (name "unconnected-(K1-Pad4)") (class "Default")
      (node (ref "K1") (pin "4") (pinfunction "4_4") (pintype "passive"))
    )
    (net (code "37") (name "unconnected-(K1-Pad5)") (class "Default")
      (node (ref "K1") (pin "5") (pinfunction "5_5") (pintype "passive"))
    )
    (net (code "38") (name "unconnected-(T1-Pad7)") (class "Default")
      (node (ref "T1") (pin "7") (pinfunction "7_7") (pintype "passive"))
    )
    (net (code "39") (name "unconnected-(T1-Pad8)") (class "Default")
      (node (ref "T1") (pin "8") (pinfunction "8_8") (pintype "passive"))
    )
  )
)
